# MCU_board_ATmega328p_v2_2.net
KiCad netlist of a schematic drawn in EAGLE
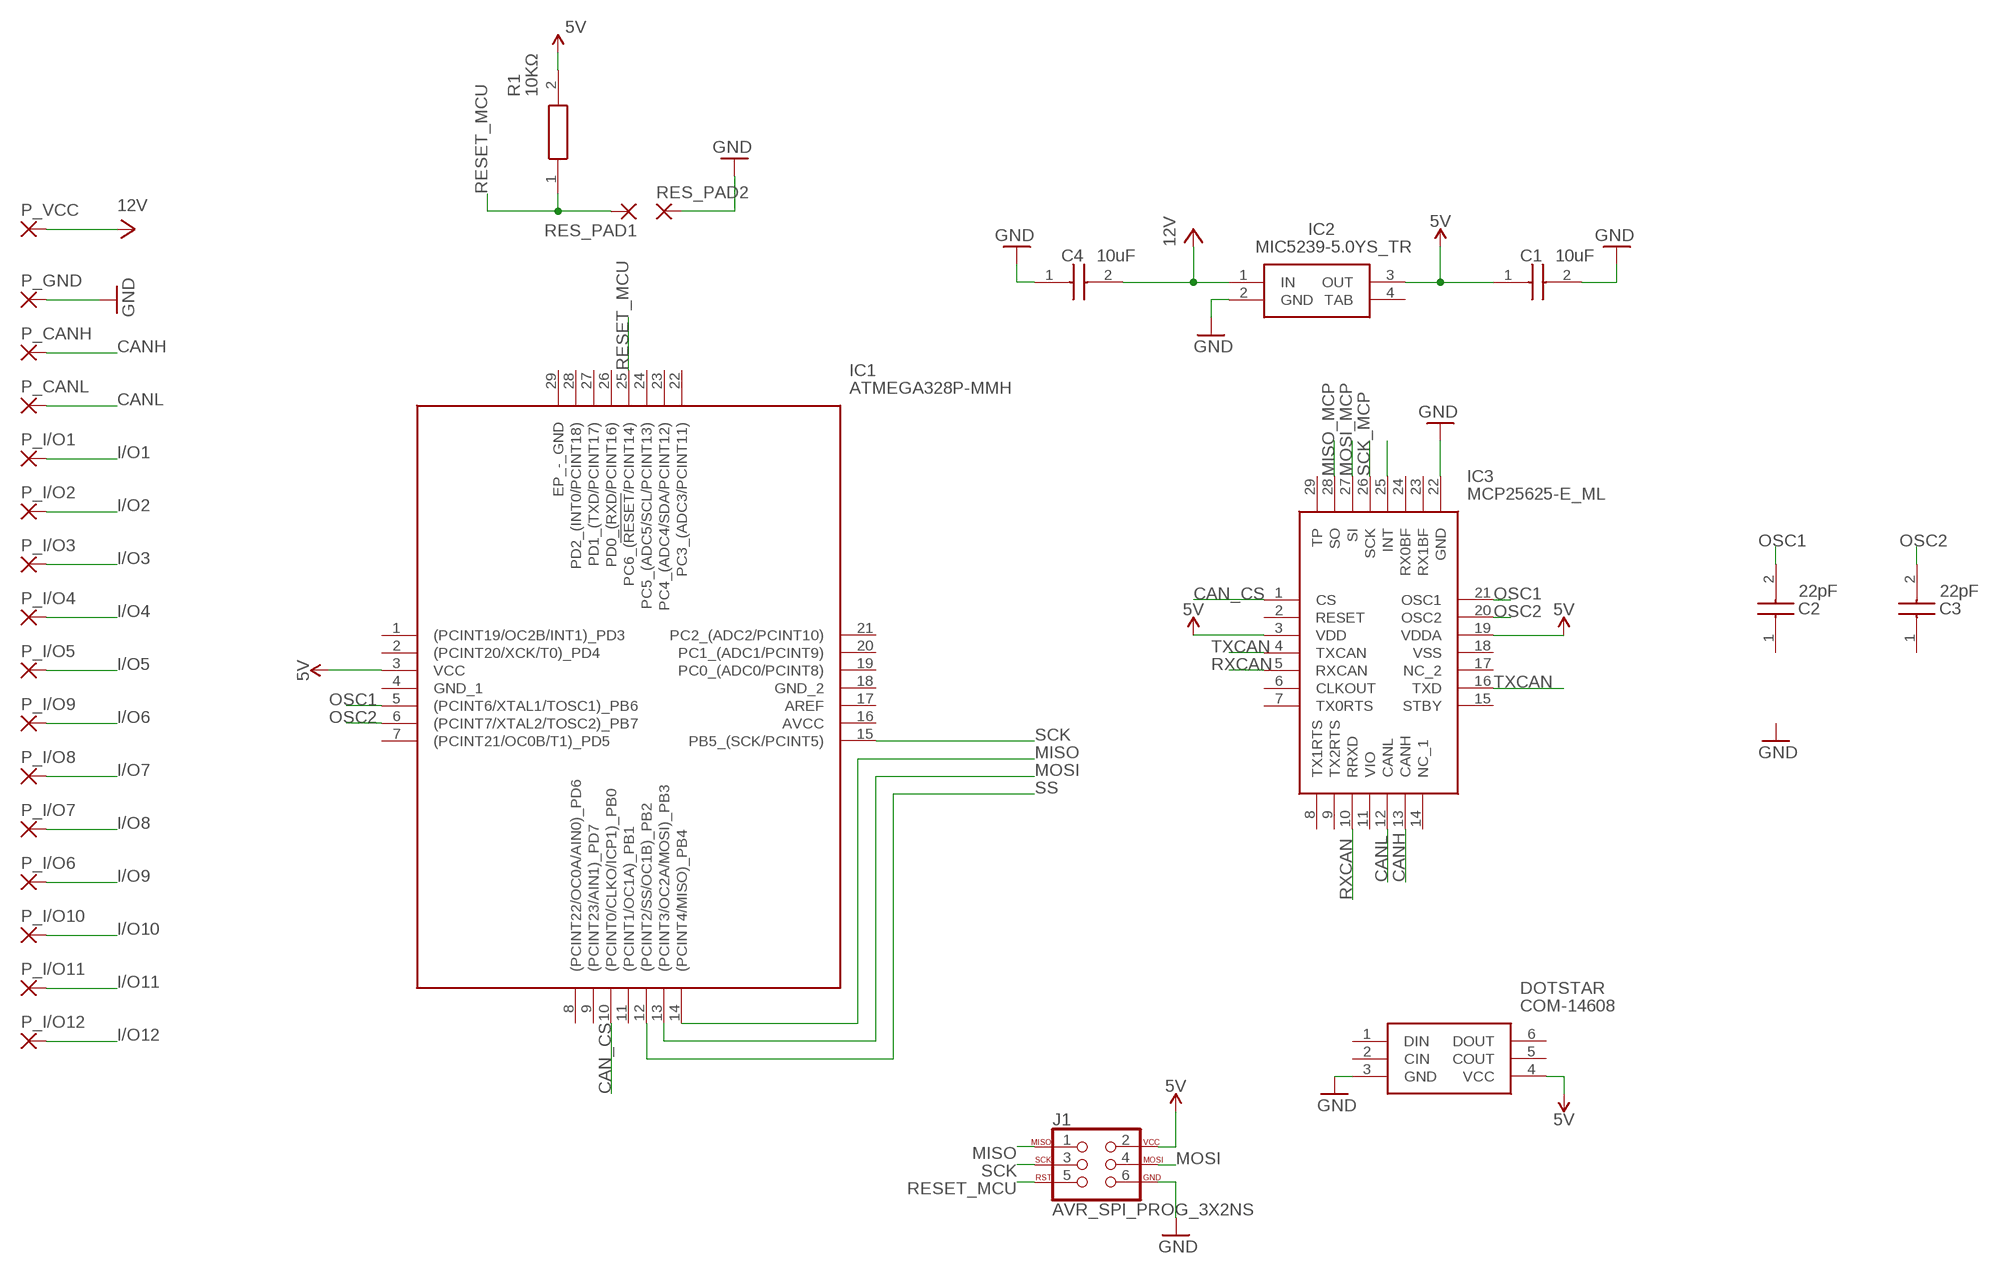
[diagram p0: schematic, sheet 1]

(export (version "E")
  (design (tool "Eeschema 10.0.6"))
  (components
    (comp (ref "C1")
      (value "10uF")
      (footprint "eagle-import:CAPPM3216X180N")
      (fields (field (name "ARROW_PART_NUMBER") "T491A106K016AT") (field (name "RS_PART_NUMBER") "1696687"))
      (libsource (lib "eagle-import") (part "T491A106K016AT"))
    )
    (comp (ref "C2")
      (value "22pF")
      (footprint "eagle-import:CAPC3216X229N")
      (fields (field (name "ARROW_PART_NUMBER") "12066D106KAT2A") (field (name "RS_PART_NUMBER") "1356756"))
      (libsource (lib "eagle-import") (part "12066D106KAT2A"))
    )
    (comp (ref "C3")
      (value "22pF")
      (footprint "eagle-import:CAPC3216X229N")
      (fields (field (name "ARROW_PART_NUMBER") "12066D106KAT2A") (field (name "RS_PART_NUMBER") "1356756"))
      (libsource (lib "eagle-import") (part "12066D106KAT2A"))
    )
    (comp (ref "C4")
      (value "10uF")
      (footprint "eagle-import:CAPPM3216X180N")
      (fields (field (name "ARROW_PART_NUMBER") "T491A106K016AT") (field (name "RS_PART_NUMBER") "1696687"))
      (libsource (lib "eagle-import") (part "T491A106K016AT"))
    )
    (comp (ref "DOTSTAR")
      (value "COM-14608")
      (footprint "eagle-import:SON75P200X200X100-6N")
      (libsource (lib "eagle-import") (part "COM-14608"))
    )
    (comp (ref "IC1")
      (value "ATMEGA328P-MMH")
      (footprint "eagle-import:QFN45P400X400X100-29N")
      (fields (field (name "RS_PART_NUMBER") "1310272P"))
      (libsource (lib "eagle-import") (part "ATMEGA328P-MMH"))
    )
    (comp (ref "IC2")
      (value "MIC5239-5.0YS_TR")
      (footprint "eagle-import:SOT230P700X170-4N")
      (fields
        (field (name "ARROW_PART_NUMBER") "MIC5239-5.0YS TR")
        (field (name "RS_PART_NUMBER") "7275535P")
      )
      (libsource (lib "eagle-import") (part "MIC5239-5.0YS_TR"))
    )
    (comp (ref "IC3")
      (value "MCP25625-E_ML")
      (footprint "eagle-import:QFN65P600X600X100-29N")
      (fields (field (name "ARROW_PART_NUMBER") "MCP25625-E/ML") (field (name "RS_PART_NUMBER") "1654104"))
      (libsource (lib "eagle-import") (part "MCP25625-E_ML"))
    )
    (comp (ref "J1")
      (value "AVR_SPI_PROG_3X2NS")
      (footprint "eagle-import:2X3-NS")
      (libsource (lib "eagle-import") (part "AVR_SPI_PROG_3X2NS"))
    )
    (comp (ref "P_CANH")
      (value "2,15/1,0")
      (footprint "eagle-import:2,15_1,0")
      (libsource (lib "eagle-import") (part "2,15/1,0"))
    )
    (comp (ref "P_CANL")
      (value "2,15/1,0")
      (footprint "eagle-import:2,15_1,0")
      (libsource (lib "eagle-import") (part "2,15/1,0"))
    )
    (comp (ref "P_GND")
      (value "2,15/1,0")
      (footprint "eagle-import:2,15_1,0")
      (libsource (lib "eagle-import") (part "2,15/1,0"))
    )
    (comp (ref "P_I/O1")
      (value "2,15/1,0")
      (footprint "eagle-import:2,15_1,0")
      (libsource (lib "eagle-import") (part "2,15/1,0"))
    )
    (comp (ref "P_I/O2")
      (value "2,15/1,0")
      (footprint "eagle-import:2,15_1,0")
      (libsource (lib "eagle-import") (part "2,15/1,0"))
    )
    (comp (ref "P_I/O3")
      (value "2,15/1,0")
      (footprint "eagle-import:2,15_1,0")
      (libsource (lib "eagle-import") (part "2,15/1,0"))
    )
    (comp (ref "P_I/O4")
      (value "2,15/1,0")
      (footprint "eagle-import:2,15_1,0")
      (libsource (lib "eagle-import") (part "2,15/1,0"))
    )
    (comp (ref "P_I/O5")
      (value "2,15/1,0")
      (footprint "eagle-import:2,15_1,0")
      (libsource (lib "eagle-import") (part "2,15/1,0"))
    )
    (comp (ref "P_I/O6")
      (value "2,15/1,0")
      (footprint "eagle-import:2,15_1,0")
      (libsource (lib "eagle-import") (part "2,15/1,0"))
    )
    (comp (ref "P_I/O7")
      (value "2,15/1,0")
      (footprint "eagle-import:2,15_1,0")
      (libsource (lib "eagle-import") (part "2,15/1,0"))
    )
    (comp (ref "P_I/O8")
      (value "2,15/1,0")
      (footprint "eagle-import:2,15_1,0")
      (libsource (lib "eagle-import") (part "2,15/1,0"))
    )
    (comp (ref "P_I/O9")
      (value "2,15/1,0")
      (footprint "eagle-import:2,15_1,0")
      (libsource (lib "eagle-import") (part "2,15/1,0"))
    )
    (comp (ref "P_I/O10")
      (value "2,15/1,0")
      (footprint "eagle-import:2,15_1,0")
      (libsource (lib "eagle-import") (part "2,15/1,0"))
    )
    (comp (ref "P_I/O11")
      (value "2,15/1,0")
      (footprint "eagle-import:2,15_1,0")
      (libsource (lib "eagle-import") (part "2,15/1,0"))
    )
    (comp (ref "P_I/O12")
      (value "2,15/1,0")
      (footprint "eagle-import:2,15_1,0")
      (libsource (lib "eagle-import") (part "2,15/1,0"))
    )
    (comp (ref "P_VCC")
      (value "2,15/1,0")
      (footprint "eagle-import:2,15_1,0")
      (libsource (lib "eagle-import") (part "2,15/1,0"))
    )
    (comp (ref "R1")
      (value "10KΩ")
      (footprint "eagle-import:RESC0603X28N")
      (fields (field (name "ARROW_PART_NUMBER") "CPF0201D10KC1") (field (name "RS_PART_NUMBER") "7549833"))
      (libsource (lib "eagle-import") (part "CPF0201D10KC1"))
    )
    (comp (ref "RES_PAD1")
      (value "SMD2")
      (footprint "eagle-import:SMD1,27-2,54")
      (libsource (lib "eagle-import") (part "SMD2"))
    )
    (comp (ref "RES_PAD2")
      (value "SMD2")
      (footprint "eagle-import:SMD1,27-2,54")
      (libsource (lib "eagle-import") (part "SMD2"))
    )
  )
  (nets
    (net (code "1") (name "/CANH") (class "Default")
      (node (ref "IC3") (pin "13") (pinfunction "CANH_13") (pintype "bidirectional"))
      (node (ref "P_CANH") (pin "1") (pinfunction "P_1") (pintype "passive"))
    )
    (net (code "2") (name "/CANL") (class "Default")
      (node (ref "IC3") (pin "12") (pinfunction "CANL_12") (pintype "bidirectional"))
      (node (ref "P_CANL") (pin "1") (pinfunction "P_1") (pintype "passive"))
    )
    (net (code "3") (name "/CAN_CS") (class "Default")
      (node (ref "IC1") (pin "10") (pinfunction "(PCINT0/CLKO/ICP1)_PB0_10") (pintype "bidirectional"))
      (node (ref "IC3") (pin "1") (pinfunction "CS_1") (pintype "input"))
    )
    (net (code "4") (name "/I{slash}O1") (class "Default")
      (node (ref "P_I/O1") (pin "1") (pinfunction "P_1") (pintype "passive"))
    )
    (net (code "5") (name "/I{slash}O2") (class "Default")
      (node (ref "P_I/O2") (pin "1") (pinfunction "P_1") (pintype "passive"))
    )
    (net (code "6") (name "/I{slash}O3") (class "Default")
      (node (ref "P_I/O3") (pin "1") (pinfunction "P_1") (pintype "passive"))
    )
    (net (code "7") (name "/I{slash}O4") (class "Default")
      (node (ref "P_I/O4") (pin "1") (pinfunction "P_1") (pintype "passive"))
    )
    (net (code "8") (name "/I{slash}O5") (class "Default")
      (node (ref "P_I/O5") (pin "1") (pinfunction "P_1") (pintype "passive"))
    )
    (net (code "9") (name "/I{slash}O6") (class "Default")
      (node (ref "P_I/O9") (pin "1") (pinfunction "P_1") (pintype "passive"))
    )
    (net (code "10") (name "/I{slash}O7") (class "Default")
      (node (ref "P_I/O8") (pin "1") (pinfunction "P_1") (pintype "passive"))
    )
    (net (code "11") (name "/I{slash}O8") (class "Default")
      (node (ref "P_I/O7") (pin "1") (pinfunction "P_1") (pintype "passive"))
    )
    (net (code "12") (name "/I{slash}O9") (class "Default")
      (node (ref "P_I/O6") (pin "1") (pinfunction "P_1") (pintype "passive"))
    )
    (net (code "13") (name "/I{slash}O10") (class "Default")
      (node (ref "P_I/O10") (pin "1") (pinfunction "P_1") (pintype "passive"))
    )
    (net (code "14") (name "/I{slash}O11") (class "Default")
      (node (ref "P_I/O11") (pin "1") (pinfunction "P_1") (pintype "passive"))
    )
    (net (code "15") (name "/I{slash}O12") (class "Default")
      (node (ref "P_I/O12") (pin "1") (pinfunction "P_1") (pintype "passive"))
    )
    (net (code "16") (name "/MISO") (class "Default")
      (node (ref "IC1") (pin "14") (pinfunction "(PCINT4/MISO)_PB4_14") (pintype "bidirectional"))
      (node (ref "J1") (pin "1") (pinfunction "1_1") (pintype "passive"))
    )
    (net (code "17") (name "/MISO_MCP") (class "Default")
      (node (ref "IC3") (pin "28") (pinfunction "SO_28") (pintype "bidirectional"))
    )
    (net (code "18") (name "/MOSI") (class "Default")
      (node (ref "IC1") (pin "13") (pinfunction "(PCINT3/OC2A/MOSI)_PB3_13") (pintype "bidirectional"))
      (node (ref "J1") (pin "4") (pinfunction "4_4") (pintype "passive"))
    )
    (net (code "19") (name "/MOSI_MCP") (class "Default")
      (node (ref "IC3") (pin "27") (pinfunction "SI_27") (pintype "bidirectional"))
    )
    (net (code "20") (name "/OSC1") (class "Default")
      (node (ref "C2") (pin "2") (pinfunction "2_2") (pintype "bidirectional"))
      (node (ref "IC1") (pin "5") (pinfunction "(PCINT6/XTAL1/TOSC1)_PB6_5") (pintype "bidirectional"))
      (node (ref "IC3") (pin "21") (pinfunction "OSC1_21") (pintype "bidirectional"))
    )
    (net (code "21") (name "/OSC2") (class "Default")
      (node (ref "C3") (pin "2") (pinfunction "2_2") (pintype "bidirectional"))
      (node (ref "IC1") (pin "6") (pinfunction "(PCINT7/XTAL2/TOSC2)_PB7_6") (pintype "bidirectional"))
      (node (ref "IC3") (pin "20") (pinfunction "OSC2_20") (pintype "bidirectional"))
    )
    (net (code "22") (name "/RESET_MCU") (class "Default")
      (node (ref "IC1") (pin "25") (pinfunction "PC6_(~{RESET}/PCINT14)_25") (pintype "bidirectional"))
      (node (ref "J1") (pin "5") (pinfunction "5_5") (pintype "passive"))
      (node (ref "R1") (pin "1") (pinfunction "1_1") (pintype "bidirectional"))
      (node (ref "RES_PAD1") (pin "1") (pinfunction "P_1") (pintype "passive"))
    )
    (net (code "23") (name "/RXCAN") (class "Default")
      (node (ref "IC3") (pin "10") (pinfunction "RRXD_10") (pintype "bidirectional"))
      (node (ref "IC3") (pin "5") (pinfunction "RXCAN_5") (pintype "bidirectional"))
    )
    (net (code "24") (name "/SCK") (class "Default")
      (node (ref "IC1") (pin "15") (pinfunction "PB5_(SCK/PCINT5)_15") (pintype "bidirectional"))
      (node (ref "J1") (pin "3") (pinfunction "3_3") (pintype "passive"))
    )
    (net (code "25") (name "/SCK_MCP") (class "Default")
      (node (ref "IC3") (pin "26") (pinfunction "SCK_26") (pintype "bidirectional"))
    )
    (net (code "26") (name "/SS") (class "Default")
      (node (ref "IC1") (pin "12") (pinfunction "(PCINT2/SS/OC1B)_PB2_12") (pintype "bidirectional"))
    )
    (net (code "27") (name "/TXCAN") (class "Default")
      (node (ref "IC3") (pin "16") (pinfunction "TXD_16") (pintype "bidirectional"))
      (node (ref "IC3") (pin "4") (pinfunction "TXCAN_4") (pintype "bidirectional"))
    )
    (net (code "28") (name "/VSS") (class "Default")
      (node (ref "IC3") (pin "18") (pinfunction "VSS_18") (pintype "power_in"))
    )
    (net (code "29") (name "5V") (class "Default")
      (node (ref "C1") (pin "1") (pinfunction "K_1") (pintype "bidirectional"))
      (node (ref "DOTSTAR") (pin "4") (pinfunction "VCC_4") (pintype "bidirectional"))
      (node (ref "IC1") (pin "3") (pinfunction "VCC_3") (pintype "bidirectional"))
      (node (ref "IC2") (pin "3") (pinfunction "OUT_3") (pintype "bidirectional"))
      (node (ref "IC3") (pin "19") (pinfunction "VDDA_19") (pintype "power_in"))
      (node (ref "IC3") (pin "3") (pinfunction "VDD_3") (pintype "power_in"))
      (node (ref "J1") (pin "2") (pinfunction "2_2") (pintype "passive"))
      (node (ref "R1") (pin "2") (pinfunction "2_2") (pintype "bidirectional"))
    )
    (net (code "30") (name "12V") (class "Default")
      (node (ref "C4") (pin "2") (pinfunction "A_2") (pintype "bidirectional"))
      (node (ref "IC2") (pin "1") (pinfunction "IN_1") (pintype "bidirectional"))
      (node (ref "P_VCC") (pin "1") (pinfunction "P_1") (pintype "passive"))
    )
    (net (code "31") (name "GND") (class "Default")
      (node (ref "C1") (pin "2") (pinfunction "A_2") (pintype "bidirectional"))
      (node (ref "C4") (pin "1") (pinfunction "K_1") (pintype "bidirectional"))
      (node (ref "DOTSTAR") (pin "3") (pinfunction "GND_3") (pintype "bidirectional"))
      (node (ref "IC2") (pin "2") (pinfunction "GND_2") (pintype "bidirectional"))
      (node (ref "IC3") (pin "22") (pinfunction "GND_22") (pintype "power_in"))
      (node (ref "J1") (pin "6") (pinfunction "6_6") (pintype "passive"))
      (node (ref "P_GND") (pin "1") (pinfunction "P_1") (pintype "passive"))
      (node (ref "RES_PAD2") (pin "1") (pinfunction "P_1") (pintype "passive"))
    )
    (net (code "32") (name "unconnected-(C2-Pad1)") (class "Default")
      (node (ref "C2") (pin "1") (pinfunction "1_1") (pintype "bidirectional"))
    )
    (net (code "33") (name "unconnected-(C3-Pad1)") (class "Default")
      (node (ref "C3") (pin "1") (pinfunction "1_1") (pintype "bidirectional"))
    )
    (net (code "34") (name "unconnected-(DOTSTAR-CIN-Pad2)") (class "Default")
      (node (ref "DOTSTAR") (pin "2") (pinfunction "CIN_2") (pintype "bidirectional"))
    )
    (net (code "35") (name "unconnected-(DOTSTAR-COUT-Pad5)") (class "Default")
      (node (ref "DOTSTAR") (pin "5") (pinfunction "COUT_5") (pintype "bidirectional"))
    )
    (net (code "36") (name "unconnected-(DOTSTAR-DIN-Pad1)") (class "Default")
      (node (ref "DOTSTAR") (pin "1") (pinfunction "DIN_1") (pintype "bidirectional"))
    )
    (net (code "37") (name "unconnected-(DOTSTAR-DOUT-Pad6)") (class "Default")
      (node (ref "DOTSTAR") (pin "6") (pinfunction "DOUT_6") (pintype "bidirectional"))
    )
    (net (code "38") (name "unconnected-(IC1-(PCINT1{slash}OC1A)_PB1-Pad11)") (class "Default")
      (node (ref "IC1") (pin "11") (pinfunction "(PCINT1/OC1A)_PB1_11") (pintype "bidirectional"))
    )
    (net (code "39") (name "unconnected-(IC1-(PCINT19{slash}OC2B{slash}INT1)_PD3-Pad1)") (class "Default")
      (node (ref "IC1") (pin "1") (pinfunction "(PCINT19/OC2B/INT1)_PD3_1") (pintype "bidirectional"))
    )
    (net (code "40") (name "unconnected-(IC1-(PCINT20{slash}XCK{slash}T0)_PD4-Pad2)") (class "Default")
      (node (ref "IC1") (pin "2") (pinfunction "(PCINT20/XCK/T0)_PD4_2") (pintype "bidirectional"))
    )
    (net (code "41") (name "unconnected-(IC1-(PCINT21{slash}OC0B{slash}T1)_PD5-Pad7)") (class "Default")
      (node (ref "IC1") (pin "7") (pinfunction "(PCINT21/OC0B/T1)_PD5_7") (pintype "bidirectional"))
    )
    (net (code "42") (name "unconnected-(IC1-(PCINT22{slash}OC0A{slash}AIN0)_PD6-Pad8)") (class "Default")
      (node (ref "IC1") (pin "8") (pinfunction "(PCINT22/OC0A/AIN0)_PD6_8") (pintype "bidirectional"))
    )
    (net (code "43") (name "unconnected-(IC1-(PCINT23{slash}AIN1)_PD7-Pad9)") (class "Default")
      (node (ref "IC1") (pin "9") (pinfunction "(PCINT23/AIN1)_PD7_9") (pintype "bidirectional"))
    )
    (net (code "44") (name "unconnected-(IC1-AREF-Pad17)") (class "Default")
      (node (ref "IC1") (pin "17") (pinfunction "AREF_17") (pintype "bidirectional"))
    )
    (net (code "45") (name "unconnected-(IC1-AVCC-Pad16)") (class "Default")
      (node (ref "IC1") (pin "16") (pinfunction "AVCC_16") (pintype "bidirectional"))
    )
    (net (code "46") (name "unconnected-(IC1-EP_-_GND-Pad29)") (class "Default")
      (node (ref "IC1") (pin "29") (pinfunction "EP_-_GND_29") (pintype "bidirectional"))
    )
    (net (code "47") (name "unconnected-(IC1-GND_1-Pad4)") (class "Default")
      (node (ref "IC1") (pin "4") (pinfunction "GND_1_4") (pintype "bidirectional"))
    )
    (net (code "48") (name "unconnected-(IC1-GND_2-Pad18)") (class "Default")
      (node (ref "IC1") (pin "18") (pinfunction "GND_2_18") (pintype "bidirectional"))
    )
    (net (code "49") (name "unconnected-(IC1-PC0_(ADC0{slash}PCINT8)-Pad19)") (class "Default")
      (node (ref "IC1") (pin "19") (pinfunction "PC0_(ADC0/PCINT8)_19") (pintype "bidirectional"))
    )
    (net (code "50") (name "unconnected-(IC1-PC1_(ADC1{slash}PCINT9)-Pad20)") (class "Default")
      (node (ref "IC1") (pin "20") (pinfunction "PC1_(ADC1/PCINT9)_20") (pintype "bidirectional"))
    )
    (net (code "51") (name "unconnected-(IC1-PC2_(ADC2{slash}PCINT10)-Pad21)") (class "Default")
      (node (ref "IC1") (pin "21") (pinfunction "PC2_(ADC2/PCINT10)_21") (pintype "bidirectional"))
    )
    (net (code "52") (name "unconnected-(IC1-PC3_(ADC3{slash}PCINT11)-Pad22)") (class "Default")
      (node (ref "IC1") (pin "22") (pinfunction "PC3_(ADC3/PCINT11)_22") (pintype "bidirectional"))
    )
    (net (code "53") (name "unconnected-(IC1-PC4_(ADC4{slash}SDA{slash}PCINT12)-Pad23)") (class "Default")
      (node (ref "IC1") (pin "23") (pinfunction "PC4_(ADC4/SDA/PCINT12)_23") (pintype "bidirectional"))
    )
    (net (code "54") (name "unconnected-(IC1-PC5_(ADC5{slash}SCL{slash}PCINT13)-Pad24)") (class "Default")
      (node (ref "IC1") (pin "24") (pinfunction "PC5_(ADC5/SCL/PCINT13)_24") (pintype "bidirectional"))
    )
    (net (code "55") (name "unconnected-(IC1-PD0_(RXD{slash}PCINT16)-Pad26)") (class "Default")
      (node (ref "IC1") (pin "26") (pinfunction "PD0_(RXD/PCINT16)_26") (pintype "bidirectional"))
    )
    (net (code "56") (name "unconnected-(IC1-PD1_(TXD{slash}PCINT17)-Pad27)") (class "Default")
      (node (ref "IC1") (pin "27") (pinfunction "PD1_(TXD/PCINT17)_27") (pintype "bidirectional"))
    )
    (net (code "57") (name "unconnected-(IC1-PD2_(INT0{slash}PCINT18)-Pad28)") (class "Default")
      (node (ref "IC1") (pin "28") (pinfunction "PD2_(INT0/PCINT18)_28") (pintype "bidirectional"))
    )
    (net (code "58") (name "unconnected-(IC2-TAB-Pad4)") (class "Default")
      (node (ref "IC2") (pin "4") (pinfunction "TAB_4") (pintype "bidirectional"))
    )
    (net (code "59") (name "unconnected-(IC3-CLKOUT-Pad6)") (class "Default")
      (node (ref "IC3") (pin "6") (pinfunction "CLKOUT_6") (pintype "output"))
    )
    (net (code "60") (name "unconnected-(IC3-INT-Pad25)") (class "Default")
      (node (ref "IC3") (pin "25") (pinfunction "INT_25") (pintype "input"))
    )
    (net (code "61") (name "unconnected-(IC3-NC_1-Pad14)") (class "Default")
      (node (ref "IC3") (pin "14") (pinfunction "NC_1_14") (pintype "bidirectional"))
    )
    (net (code "62") (name "unconnected-(IC3-NC_2-Pad17)") (class "Default")
      (node (ref "IC3") (pin "17") (pinfunction "NC_2_17") (pintype "bidirectional"))
    )
    (net (code "63") (name "unconnected-(IC3-RESET-Pad2)") (class "Default")
      (node (ref "IC3") (pin "2") (pinfunction "RESET_2") (pintype "bidirectional"))
    )
    (net (code "64") (name "unconnected-(IC3-RX0BF-Pad24)") (class "Default")
      (node (ref "IC3") (pin "24") (pinfunction "RX0BF_24") (pintype "bidirectional"))
    )
    (net (code "65") (name "unconnected-(IC3-RX1BF-Pad23)") (class "Default")
      (node (ref "IC3") (pin "23") (pinfunction "RX1BF_23") (pintype "bidirectional"))
    )
    (net (code "66") (name "unconnected-(IC3-STBY-Pad15)") (class "Default")
      (node (ref "IC3") (pin "15") (pinfunction "STBY_15") (pintype "bidirectional"))
    )
    (net (code "67") (name "unconnected-(IC3-TP-Pad29)") (class "Default")
      (node (ref "IC3") (pin "29") (pinfunction "TP_29") (pintype "bidirectional"))
    )
    (net (code "68") (name "unconnected-(IC3-TX0RTS-Pad7)") (class "Default")
      (node (ref "IC3") (pin "7") (pinfunction "TX0RTS_7") (pintype "bidirectional"))
    )
    (net (code "69") (name "unconnected-(IC3-TX1RTS-Pad8)") (class "Default")
      (node (ref "IC3") (pin "8") (pinfunction "TX1RTS_8") (pintype "bidirectional"))
    )
    (net (code "70") (name "unconnected-(IC3-TX2RTS-Pad9)") (class "Default")
      (node (ref "IC3") (pin "9") (pinfunction "TX2RTS_9") (pintype "bidirectional"))
    )
    (net (code "71") (name "unconnected-(IC3-VIO-Pad11)") (class "Default")
      (node (ref "IC3") (pin "11") (pinfunction "VIO_11") (pintype "bidirectional"))
    )
  )
)
